# NB2_DBCON.net
KiCad netlist of a schematic drawn in Altium Designer
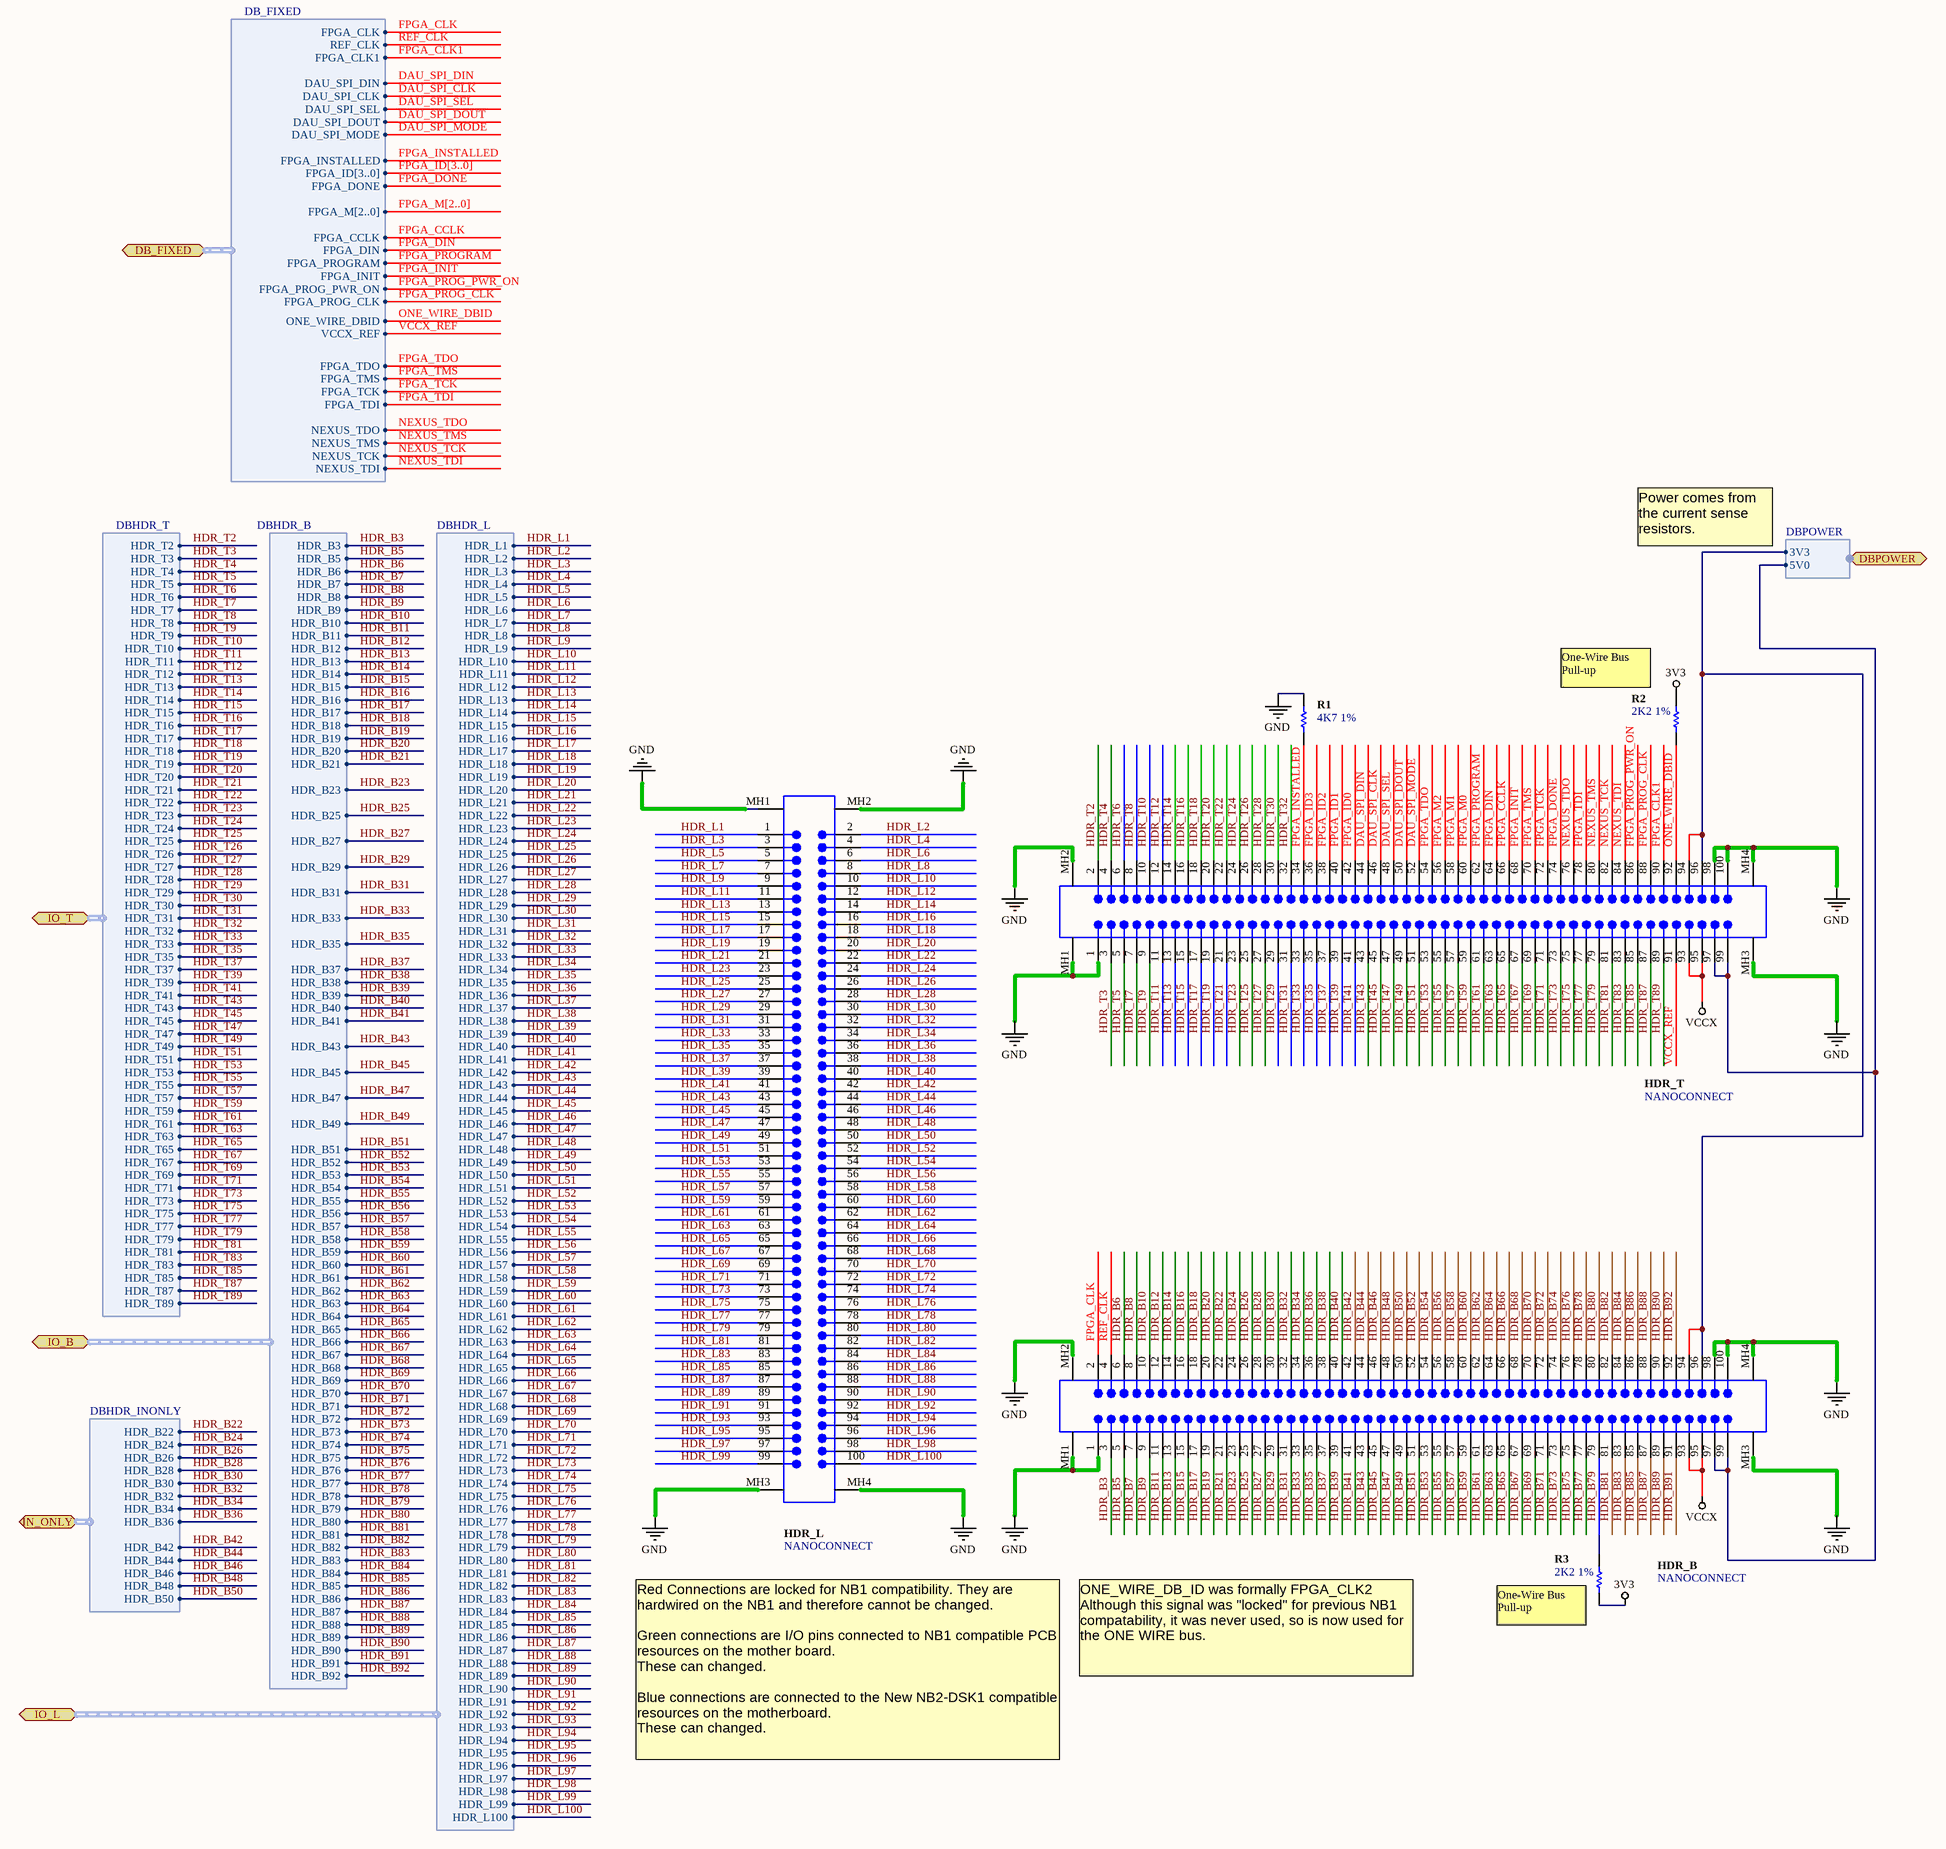
[diagram p0: NB2_DBCON.SchDoc]

(export (version "E")
  (design (tool "Eeschema 10.0.6"))
  (components
    (comp (ref "HDR_B")
      (value "NANOCONNECT")
      (footprint "53751")
      (description "Connector, Molex Docking Station 100 Pin Female 53751")
      (libsource (lib "altium-import") (part "root_1_CON-DOCKSTAT-100-F-STR_"))
    )
    (comp (ref "HDR_L")
      (value "NANOCONNECT")
      (footprint "53751")
      (description "Connector, Molex Docking Station 100 Pin Female 53751")
      (libsource (lib "altium-import") (part "root_0_CON-DOCKSTAT-100-F-STR_"))
    )
    (comp (ref "HDR_T")
      (value "NANOCONNECT")
      (footprint "53751")
      (description "Connector, Molex Docking Station 100 Pin Female 53751")
      (libsource (lib "altium-import") (part "root_1_CON-DOCKSTAT-100-F-STR_"))
    )
    (comp (ref "R1")
      (value "4K7 1%")
      (footprint "RESC1005-STAR")
      (description "Resistor, 4K7 1% 0402 (1005)")
      (fields (field (name "TOLERANCE") "1 %"))
      (libsource (lib "altium-import") (part "root_2_RES_"))
    )
    (comp (ref "R2")
      (value "2K2 1%")
      (footprint "RESC1005-STAR")
      (description "Resistor, 2K2 1% 0402 (1005)")
      (fields (field (name "TOLERANCE") "1 %"))
      (libsource (lib "altium-import") (part "root_2_RES_"))
    )
    (comp (ref "R3")
      (value "2K2 1%")
      (footprint "RESC1005-STAR")
      (description "Resistor, 2K2 1% 0402 (1005)")
      (fields (field (name "TOLERANCE") "1 %"))
      (libsource (lib "altium-import") (part "root_2_RES_"))
    )
  )
  (nets
    (net (code "7") (name "/DAU_SPI_CLK") (class "Default")
      (node (ref "HDR_T") (pin "46") (pinfunction "46_46") (pintype "passive"))
    )
    (net (code "8") (name "/DAU_SPI_DIN") (class "Default")
      (node (ref "HDR_T") (pin "44") (pinfunction "44_44") (pintype "passive"))
    )
    (net (code "9") (name "/DAU_SPI_DOUT") (class "Default")
      (node (ref "HDR_T") (pin "50") (pinfunction "50_50") (pintype "passive"))
    )
    (net (code "10") (name "/DAU_SPI_MODE") (class "Default")
      (node (ref "HDR_T") (pin "52") (pinfunction "52_52") (pintype "passive"))
    )
    (net (code "11") (name "/DAU_SPI_SEL") (class "Default")
      (node (ref "HDR_T") (pin "48") (pinfunction "48_48") (pintype "passive"))
    )
    (net (code "12") (name "/FPGA_CCLK") (class "Default")
      (node (ref "HDR_T") (pin "66") (pinfunction "66_66") (pintype "passive"))
    )
    (net (code "13") (name "/FPGA_CLK") (class "Default")
      (node (ref "HDR_B") (pin "2") (pinfunction "2_2") (pintype "passive"))
    )
    (net (code "14") (name "/FPGA_CLK1") (class "Default")
      (node (ref "HDR_T") (pin "90") (pinfunction "90_90") (pintype "passive"))
    )
    (net (code "15") (name "/FPGA_DIN") (class "Default")
      (node (ref "HDR_T") (pin "64") (pinfunction "64_64") (pintype "passive"))
    )
    (net (code "16") (name "/FPGA_DONE") (class "Default")
      (node (ref "HDR_T") (pin "74") (pinfunction "74_74") (pintype "passive"))
    )
    (net (code "17") (name "/FPGA_ID0") (class "Default")
      (node (ref "HDR_T") (pin "42") (pinfunction "42_42") (pintype "passive"))
    )
    (net (code "18") (name "/FPGA_ID1") (class "Default")
      (node (ref "HDR_T") (pin "40") (pinfunction "40_40") (pintype "passive"))
    )
    (net (code "19") (name "/FPGA_ID2") (class "Default")
      (node (ref "HDR_T") (pin "38") (pinfunction "38_38") (pintype "passive"))
    )
    (net (code "20") (name "/FPGA_ID3") (class "Default")
      (node (ref "HDR_T") (pin "36") (pinfunction "36_36") (pintype "passive"))
    )
    (net (code "22") (name "/FPGA_INIT") (class "Default")
      (node (ref "HDR_T") (pin "68") (pinfunction "68_68") (pintype "passive"))
    )
    (net (code "23") (name "/FPGA_INSTALLED") (class "Default")
      (node (ref "HDR_T") (pin "34") (pinfunction "34_34") (pintype "passive"))
      (node (ref "R1") (pin "1") (pinfunction "1_1") (pintype "passive"))
    )
    (net (code "24") (name "/FPGA_M0") (class "Default")
      (node (ref "HDR_T") (pin "60") (pinfunction "60_60") (pintype "passive"))
    )
    (net (code "25") (name "/FPGA_M1") (class "Default")
      (node (ref "HDR_T") (pin "58") (pinfunction "58_58") (pintype "passive"))
    )
    (net (code "26") (name "/FPGA_M2") (class "Default")
      (node (ref "HDR_T") (pin "56") (pinfunction "56_56") (pintype "passive"))
    )
    (net (code "28") (name "/FPGA_PROGRAM") (class "Default")
      (node (ref "HDR_T") (pin "62") (pinfunction "62_62") (pintype "passive"))
    )
    (net (code "29") (name "/FPGA_PROG_CLK") (class "Default")
      (node (ref "HDR_T") (pin "88") (pinfunction "88_88") (pintype "passive"))
    )
    (net (code "30") (name "/FPGA_PROG_PWR_ON") (class "Default")
      (node (ref "HDR_T") (pin "86") (pinfunction "86_86") (pintype "passive"))
    )
    (net (code "31") (name "/FPGA_TCK") (class "Default")
      (node (ref "HDR_T") (pin "72") (pinfunction "72_72") (pintype "passive"))
    )
    (net (code "32") (name "/FPGA_TDI") (class "Default")
      (node (ref "HDR_T") (pin "78") (pinfunction "78_78") (pintype "passive"))
    )
    (net (code "33") (name "/FPGA_TDO") (class "Default")
      (node (ref "HDR_T") (pin "54") (pinfunction "54_54") (pintype "passive"))
    )
    (net (code "34") (name "/FPGA_TMS") (class "Default")
      (node (ref "HDR_T") (pin "70") (pinfunction "70_70") (pintype "passive"))
    )
    (net (code "35") (name "/HDR_B3") (class "Default")
      (node (ref "HDR_B") (pin "3") (pinfunction "3_3") (pintype "passive"))
    )
    (net (code "36") (name "/HDR_B5") (class "Default")
      (node (ref "HDR_B") (pin "5") (pinfunction "5_5") (pintype "passive"))
    )
    (net (code "37") (name "/HDR_B6") (class "Default")
      (node (ref "HDR_B") (pin "6") (pinfunction "6_6") (pintype "passive"))
    )
    (net (code "38") (name "/HDR_B7") (class "Default")
      (node (ref "HDR_B") (pin "7") (pinfunction "7_7") (pintype "passive"))
    )
    (net (code "39") (name "/HDR_B8") (class "Default")
      (node (ref "HDR_B") (pin "8") (pinfunction "8_8") (pintype "passive"))
    )
    (net (code "40") (name "/HDR_B9") (class "Default")
      (node (ref "HDR_B") (pin "9") (pinfunction "9_9") (pintype "passive"))
    )
    (net (code "41") (name "/HDR_B10") (class "Default")
      (node (ref "HDR_B") (pin "10") (pinfunction "10_10") (pintype "passive"))
    )
    (net (code "42") (name "/HDR_B11") (class "Default")
      (node (ref "HDR_B") (pin "11") (pinfunction "11_11") (pintype "passive"))
    )
    (net (code "43") (name "/HDR_B12") (class "Default")
      (node (ref "HDR_B") (pin "12") (pinfunction "12_12") (pintype "passive"))
    )
    (net (code "44") (name "/HDR_B13") (class "Default")
      (node (ref "HDR_B") (pin "13") (pinfunction "13_13") (pintype "passive"))
    )
    (net (code "45") (name "/HDR_B14") (class "Default")
      (node (ref "HDR_B") (pin "14") (pinfunction "14_14") (pintype "passive"))
    )
    (net (code "46") (name "/HDR_B15") (class "Default")
      (node (ref "HDR_B") (pin "15") (pinfunction "15_15") (pintype "passive"))
    )
    (net (code "47") (name "/HDR_B16") (class "Default")
      (node (ref "HDR_B") (pin "16") (pinfunction "16_16") (pintype "passive"))
    )
    (net (code "48") (name "/HDR_B17") (class "Default")
      (node (ref "HDR_B") (pin "17") (pinfunction "17_17") (pintype "passive"))
    )
    (net (code "49") (name "/HDR_B18") (class "Default")
      (node (ref "HDR_B") (pin "18") (pinfunction "18_18") (pintype "passive"))
    )
    (net (code "50") (name "/HDR_B19") (class "Default")
      (node (ref "HDR_B") (pin "19") (pinfunction "19_19") (pintype "passive"))
    )
    (net (code "51") (name "/HDR_B20") (class "Default")
      (node (ref "HDR_B") (pin "20") (pinfunction "20_20") (pintype "passive"))
    )
    (net (code "52") (name "/HDR_B21") (class "Default")
      (node (ref "HDR_B") (pin "21") (pinfunction "21_21") (pintype "passive"))
    )
    (net (code "53") (name "/HDR_B22") (class "Default")
      (node (ref "HDR_B") (pin "22") (pinfunction "22_22") (pintype "passive"))
    )
    (net (code "54") (name "/HDR_B23") (class "Default")
      (node (ref "HDR_B") (pin "23") (pinfunction "23_23") (pintype "passive"))
    )
    (net (code "55") (name "/HDR_B24") (class "Default")
      (node (ref "HDR_B") (pin "24") (pinfunction "24_24") (pintype "passive"))
    )
    (net (code "56") (name "/HDR_B25") (class "Default")
      (node (ref "HDR_B") (pin "25") (pinfunction "25_25") (pintype "passive"))
    )
    (net (code "57") (name "/HDR_B26") (class "Default")
      (node (ref "HDR_B") (pin "26") (pinfunction "26_26") (pintype "passive"))
    )
    (net (code "58") (name "/HDR_B27") (class "Default")
      (node (ref "HDR_B") (pin "27") (pinfunction "27_27") (pintype "passive"))
    )
    (net (code "59") (name "/HDR_B28") (class "Default")
      (node (ref "HDR_B") (pin "28") (pinfunction "28_28") (pintype "passive"))
    )
    (net (code "60") (name "/HDR_B29") (class "Default")
      (node (ref "HDR_B") (pin "29") (pinfunction "29_29") (pintype "passive"))
    )
    (net (code "61") (name "/HDR_B30") (class "Default")
      (node (ref "HDR_B") (pin "30") (pinfunction "30_30") (pintype "passive"))
    )
    (net (code "62") (name "/HDR_B31") (class "Default")
      (node (ref "HDR_B") (pin "31") (pinfunction "31_31") (pintype "passive"))
    )
    (net (code "63") (name "/HDR_B32") (class "Default")
      (node (ref "HDR_B") (pin "32") (pinfunction "32_32") (pintype "passive"))
    )
    (net (code "64") (name "/HDR_B33") (class "Default")
      (node (ref "HDR_B") (pin "33") (pinfunction "33_33") (pintype "passive"))
    )
    (net (code "65") (name "/HDR_B34") (class "Default")
      (node (ref "HDR_B") (pin "34") (pinfunction "34_34") (pintype "passive"))
    )
    (net (code "66") (name "/HDR_B35") (class "Default")
      (node (ref "HDR_B") (pin "35") (pinfunction "35_35") (pintype "passive"))
    )
    (net (code "67") (name "/HDR_B36") (class "Default")
      (node (ref "HDR_B") (pin "36") (pinfunction "36_36") (pintype "passive"))
    )
    (net (code "68") (name "/HDR_B37") (class "Default")
      (node (ref "HDR_B") (pin "37") (pinfunction "37_37") (pintype "passive"))
    )
    (net (code "69") (name "/HDR_B38") (class "Default")
      (node (ref "HDR_B") (pin "38") (pinfunction "38_38") (pintype "passive"))
    )
    (net (code "70") (name "/HDR_B39") (class "Default")
      (node (ref "HDR_B") (pin "39") (pinfunction "39_39") (pintype "passive"))
    )
    (net (code "71") (name "/HDR_B40") (class "Default")
      (node (ref "HDR_B") (pin "40") (pinfunction "40_40") (pintype "passive"))
    )
    (net (code "72") (name "/HDR_B41") (class "Default")
      (node (ref "HDR_B") (pin "41") (pinfunction "41_41") (pintype "passive"))
    )
    (net (code "73") (name "/HDR_B42") (class "Default")
      (node (ref "HDR_B") (pin "42") (pinfunction "42_42") (pintype "passive"))
    )
    (net (code "74") (name "/HDR_B43") (class "Default")
      (node (ref "HDR_B") (pin "43") (pinfunction "43_43") (pintype "passive"))
    )
    (net (code "75") (name "/HDR_B44") (class "Default")
      (node (ref "HDR_B") (pin "44") (pinfunction "44_44") (pintype "passive"))
    )
    (net (code "76") (name "/HDR_B45") (class "Default")
      (node (ref "HDR_B") (pin "45") (pinfunction "45_45") (pintype "passive"))
    )
    (net (code "77") (name "/HDR_B46") (class "Default")
      (node (ref "HDR_B") (pin "46") (pinfunction "46_46") (pintype "passive"))
    )
    (net (code "78") (name "/HDR_B47") (class "Default")
      (node (ref "HDR_B") (pin "47") (pinfunction "47_47") (pintype "passive"))
    )
    (net (code "79") (name "/HDR_B48") (class "Default")
      (node (ref "HDR_B") (pin "48") (pinfunction "48_48") (pintype "passive"))
    )
    (net (code "80") (name "/HDR_B49") (class "Default")
      (node (ref "HDR_B") (pin "49") (pinfunction "49_49") (pintype "passive"))
    )
    (net (code "81") (name "/HDR_B50") (class "Default")
      (node (ref "HDR_B") (pin "50") (pinfunction "50_50") (pintype "passive"))
    )
    (net (code "82") (name "/HDR_B51") (class "Default")
      (node (ref "HDR_B") (pin "51") (pinfunction "51_51") (pintype "passive"))
    )
    (net (code "83") (name "/HDR_B52") (class "Default")
      (node (ref "HDR_B") (pin "52") (pinfunction "52_52") (pintype "passive"))
    )
    (net (code "84") (name "/HDR_B53") (class "Default")
      (node (ref "HDR_B") (pin "53") (pinfunction "53_53") (pintype "passive"))
    )
    (net (code "85") (name "/HDR_B54") (class "Default")
      (node (ref "HDR_B") (pin "54") (pinfunction "54_54") (pintype "passive"))
    )
    (net (code "86") (name "/HDR_B55") (class "Default")
      (node (ref "HDR_B") (pin "55") (pinfunction "55_55") (pintype "passive"))
    )
    (net (code "87") (name "/HDR_B56") (class "Default")
      (node (ref "HDR_B") (pin "56") (pinfunction "56_56") (pintype "passive"))
    )
    (net (code "88") (name "/HDR_B57") (class "Default")
      (node (ref "HDR_B") (pin "57") (pinfunction "57_57") (pintype "passive"))
    )
    (net (code "89") (name "/HDR_B58") (class "Default")
      (node (ref "HDR_B") (pin "58") (pinfunction "58_58") (pintype "passive"))
    )
    (net (code "90") (name "/HDR_B59") (class "Default")
      (node (ref "HDR_B") (pin "59") (pinfunction "59_59") (pintype "passive"))
    )
    (net (code "91") (name "/HDR_B60") (class "Default")
      (node (ref "HDR_B") (pin "60") (pinfunction "60_60") (pintype "passive"))
    )
    (net (code "92") (name "/HDR_B61") (class "Default")
      (node (ref "HDR_B") (pin "61") (pinfunction "61_61") (pintype "passive"))
    )
    (net (code "93") (name "/HDR_B62") (class "Default")
      (node (ref "HDR_B") (pin "62") (pinfunction "62_62") (pintype "passive"))
    )
    (net (code "94") (name "/HDR_B63") (class "Default")
      (node (ref "HDR_B") (pin "63") (pinfunction "63_63") (pintype "passive"))
    )
    (net (code "95") (name "/HDR_B64") (class "Default")
      (node (ref "HDR_B") (pin "64") (pinfunction "64_64") (pintype "passive"))
    )
    (net (code "96") (name "/HDR_B65") (class "Default")
      (node (ref "HDR_B") (pin "65") (pinfunction "65_65") (pintype "passive"))
    )
    (net (code "97") (name "/HDR_B66") (class "Default")
      (node (ref "HDR_B") (pin "66") (pinfunction "66_66") (pintype "passive"))
    )
    (net (code "98") (name "/HDR_B67") (class "Default")
      (node (ref "HDR_B") (pin "67") (pinfunction "67_67") (pintype "passive"))
    )
    (net (code "99") (name "/HDR_B68") (class "Default")
      (node (ref "HDR_B") (pin "68") (pinfunction "68_68") (pintype "passive"))
    )
    (net (code "100") (name "/HDR_B69") (class "Default")
      (node (ref "HDR_B") (pin "69") (pinfunction "69_69") (pintype "passive"))
    )
    (net (code "101") (name "/HDR_B70") (class "Default")
      (node (ref "HDR_B") (pin "70") (pinfunction "70_70") (pintype "passive"))
    )
    (net (code "102") (name "/HDR_B71") (class "Default")
      (node (ref "HDR_B") (pin "71") (pinfunction "71_71") (pintype "passive"))
    )
    (net (code "103") (name "/HDR_B72") (class "Default")
      (node (ref "HDR_B") (pin "72") (pinfunction "72_72") (pintype "passive"))
    )
    (net (code "104") (name "/HDR_B73") (class "Default")
      (node (ref "HDR_B") (pin "73") (pinfunction "73_73") (pintype "passive"))
    )
    (net (code "105") (name "/HDR_B74") (class "Default")
      (node (ref "HDR_B") (pin "74") (pinfunction "74_74") (pintype "passive"))
    )
    (net (code "106") (name "/HDR_B75") (class "Default")
      (node (ref "HDR_B") (pin "75") (pinfunction "75_75") (pintype "passive"))
    )
    (net (code "107") (name "/HDR_B76") (class "Default")
      (node (ref "HDR_B") (pin "76") (pinfunction "76_76") (pintype "passive"))
    )
    (net (code "108") (name "/HDR_B77") (class "Default")
      (node (ref "HDR_B") (pin "77") (pinfunction "77_77") (pintype "passive"))
    )
    (net (code "109") (name "/HDR_B78") (class "Default")
      (node (ref "HDR_B") (pin "78") (pinfunction "78_78") (pintype "passive"))
    )
    (net (code "110") (name "/HDR_B79") (class "Default")
      (node (ref "HDR_B") (pin "79") (pinfunction "79_79") (pintype "passive"))
      (node (ref "R3") (pin "2") (pinfunction "2_2") (pintype "passive"))
    )
    (net (code "111") (name "/HDR_B80") (class "Default")
      (node (ref "HDR_B") (pin "80") (pinfunction "80_80") (pintype "passive"))
    )
    (net (code "112") (name "/HDR_B81") (class "Default")
      (node (ref "HDR_B") (pin "81") (pinfunction "81_81") (pintype "passive"))
    )
    (net (code "113") (name "/HDR_B82") (class "Default")
      (node (ref "HDR_B") (pin "82") (pinfunction "82_82") (pintype "passive"))
    )
    (net (code "114") (name "/HDR_B83") (class "Default")
      (node (ref "HDR_B") (pin "83") (pinfunction "83_83") (pintype "passive"))
    )
    (net (code "115") (name "/HDR_B84") (class "Default")
      (node (ref "HDR_B") (pin "84") (pinfunction "84_84") (pintype "passive"))
    )
    (net (code "116") (name "/HDR_B85") (class "Default")
      (node (ref "HDR_B") (pin "85") (pinfunction "85_85") (pintype "passive"))
    )
    (net (code "117") (name "/HDR_B86") (class "Default")
      (node (ref "HDR_B") (pin "86") (pinfunction "86_86") (pintype "passive"))
    )
    (net (code "118") (name "/HDR_B87") (class "Default")
      (node (ref "HDR_B") (pin "87") (pinfunction "87_87") (pintype "passive"))
    )
    (net (code "119") (name "/HDR_B88") (class "Default")
      (node (ref "HDR_B") (pin "88") (pinfunction "88_88") (pintype "passive"))
    )
    (net (code "120") (name "/HDR_B89") (class "Default")
      (node (ref "HDR_B") (pin "89") (pinfunction "89_89") (pintype "passive"))
    )
    (net (code "121") (name "/HDR_B90") (class "Default")
      (node (ref "HDR_B") (pin "90") (pinfunction "90_90") (pintype "passive"))
    )
    (net (code "122") (name "/HDR_B91") (class "Default")
      (node (ref "HDR_B") (pin "91") (pinfunction "91_91") (pintype "passive"))
    )
    (net (code "123") (name "/HDR_B92") (class "Default")
      (node (ref "HDR_B") (pin "92") (pinfunction "92_92") (pintype "passive"))
    )
    (net (code "124") (name "/HDR_L1") (class "Default")
      (node (ref "HDR_L") (pin "1") (pinfunction "1_1") (pintype "passive"))
    )
    (net (code "125") (name "/HDR_L2") (class "Default")
      (node (ref "HDR_L") (pin "2") (pinfunction "2_2") (pintype "passive"))
    )
    (net (code "126") (name "/HDR_L3") (class "Default")
      (node (ref "HDR_L") (pin "3") (pinfunction "3_3") (pintype "passive"))
    )
    (net (code "127") (name "/HDR_L4") (class "Default")
      (node (ref "HDR_L") (pin "4") (pinfunction "4_4") (pintype "passive"))
    )
    (net (code "128") (name "/HDR_L5") (class "Default")
      (node (ref "HDR_L") (pin "5") (pinfunction "5_5") (pintype "passive"))
    )
    (net (code "129") (name "/HDR_L6") (class "Default")
      (node (ref "HDR_L") (pin "6") (pinfunction "6_6") (pintype "passive"))
    )
    (net (code "130") (name "/HDR_L7") (class "Default")
      (node (ref "HDR_L") (pin "7") (pinfunction "7_7") (pintype "passive"))
    )
    (net (code "131") (name "/HDR_L8") (class "Default")
      (node (ref "HDR_L") (pin "8") (pinfunction "8_8") (pintype "passive"))
    )
    (net (code "132") (name "/HDR_L9") (class "Default")
      (node (ref "HDR_L") (pin "9") (pinfunction "9_9") (pintype "passive"))
    )
    (net (code "133") (name "/HDR_L10") (class "Default")
      (node (ref "HDR_L") (pin "10") (pinfunction "10_10") (pintype "passive"))
    )
    (net (code "134") (name "/HDR_L11") (class "Default")
      (node (ref "HDR_L") (pin "11") (pinfunction "11_11") (pintype "passive"))
    )
    (net (code "135") (name "/HDR_L12") (class "Default")
      (node (ref "HDR_L") (pin "12") (pinfunction "12_12") (pintype "passive"))
    )
    (net (code "136") (name "/HDR_L13") (class "Default")
      (node (ref "HDR_L") (pin "13") (pinfunction "13_13") (pintype "passive"))
    )
    (net (code "137") (name "/HDR_L14") (class "Default")
      (node (ref "HDR_L") (pin "14") (pinfunction "14_14") (pintype "passive"))
    )
    (net (code "138") (name "/HDR_L15") (class "Default")
      (node (ref "HDR_L") (pin "15") (pinfunction "15_15") (pintype "passive"))
    )
    (net (code "139") (name "/HDR_L16") (class "Default")
      (node (ref "HDR_L") (pin "16") (pinfunction "16_16") (pintype "passive"))
    )
    (net (code "140") (name "/HDR_L17") (class "Default")
      (node (ref "HDR_L") (pin "17") (pinfunction "17_17") (pintype "passive"))
    )
    (net (code "141") (name "/HDR_L18") (class "Default")
      (node (ref "HDR_L") (pin "18") (pinfunction "18_18") (pintype "passive"))
    )
    (net (code "142") (name "/HDR_L19") (class "Default")
      (node (ref "HDR_L") (pin "19") (pinfunction "19_19") (pintype "passive"))
    )
    (net (code "143") (name "/HDR_L20") (class "Default")
      (node (ref "HDR_L") (pin "20") (pinfunction "20_20") (pintype "passive"))
    )
    (net (code "144") (name "/HDR_L21") (class "Default")
      (node (ref "HDR_L") (pin "21") (pinfunction "21_21") (pintype "passive"))
    )
    (net (code "145") (name "/HDR_L22") (class "Default")
      (node (ref "HDR_L") (pin "22") (pinfunction "22_22") (pintype "passive"))
    )
    (net (code "146") (name "/HDR_L23") (class "Default")
      (node (ref "HDR_L") (pin "23") (pinfunction "23_23") (pintype "passive"))
    )
    (net (code "147") (name "/HDR_L24") (class "Default")
      (node (ref "HDR_L") (pin "24") (pinfunction "24_24") (pintype "passive"))
    )
    (net (code "148") (name "/HDR_L25") (class "Default")
      (node (ref "HDR_L") (pin "25") (pinfunction "25_25") (pintype "passive"))
    )
    (net (code "149") (name "/HDR_L26") (class "Default")
      (node (ref "HDR_L") (pin "26") (pinfunction "26_26") (pintype "passive"))
    )
    (net (code "150") (name "/HDR_L27") (class "Default")
      (node (ref "HDR_L") (pin "27") (pinfunction "27_27") (pintype "passive"))
    )
    (net (code "151") (name "/HDR_L28") (class "Default")
      (node (ref "HDR_L") (pin "28") (pinfunction "28_28") (pintype "passive"))
    )
    (net (code "152") (name "/HDR_L29") (class "Default")
      (node (ref "HDR_L") (pin "29") (pinfunction "29_29") (pintype "passive"))
    )
    (net (code "153") (name "/HDR_L30") (class "Default")
      (node (ref "HDR_L") (pin "30") (pinfunction "30_30") (pintype "passive"))
    )
    (net (code "154") (name "/HDR_L31") (class "Default")
      (node (ref "HDR_L") (pin "31") (pinfunction "31_31") (pintype "passive"))
    )
    (net (code "155") (name "/HDR_L32") (class "Default")
      (node (ref "HDR_L") (pin "32") (pinfunction "32_32") (pintype "passive"))
    )
    (net (code "156") (name "/HDR_L33") (class "Default")
      (node (ref "HDR_L") (pin "33") (pinfunction "33_33") (pintype "passive"))
    )
    (net (code "157") (name "/HDR_L34") (class "Default")
      (node (ref "HDR_L") (pin "34") (pinfunction "34_34") (pintype "passive"))
    )
    (net (code "158") (name "/HDR_L35") (class "Default")
      (node (ref "HDR_L") (pin "35") (pinfunction "35_35") (pintype "passive"))
    )
    (net (code "159") (name "/HDR_L36") (class "Default")
      (node (ref "HDR_L") (pin "36") (pinfunction "36_36") (pintype "passive"))
    )
    (net (code "160") (name "/HDR_L37") (class "Default")
      (node (ref "HDR_L") (pin "37") (pinfunction "37_37") (pintype "passive"))
    )
    (net (code "161") (name "/HDR_L38") (class "Default")
      (node (ref "HDR_L") (pin "38") (pinfunction "38_38") (pintype "passive"))
    )
    (net (code "162") (name "/HDR_L39") (class "Default")
      (node (ref "HDR_L") (pin "39") (pinfunction "39_39") (pintype "passive"))
    )
    (net (code "163") (name "/HDR_L40") (class "Default")
      (node (ref "HDR_L") (pin "40") (pinfunction "40_40") (pintype "passive"))
    )
    (net (code "164") (name "/HDR_L41") (class "Default")
      (node (ref "HDR_L") (pin "41") (pinfunction "41_41") (pintype "passive"))
    )
    (net (code "165") (name "/HDR_L42") (class "Default")
      (node (ref "HDR_L") (pin "42") (pinfunction "42_42") (pintype "passive"))
    )
    (net (code "166") (name "/HDR_L43") (class "Default")
      (node (ref "HDR_L") (pin "43") (pinfunction "43_43") (pintype "passive"))
    )
    (net (code "167") (name "/HDR_L44") (class "Default")
      (node (ref "HDR_L") (pin "44") (pinfunction "44_44") (pintype "passive"))
    )
    (net (code "168") (name "/HDR_L45") (class "Default")
      (node (ref "HDR_L") (pin "45") (pinfunction "45_45") (pintype "passive"))
    )
    (net (code "169") (name "/HDR_L46") (class "Default")
      (node (ref "HDR_L") (pin "46") (pinfunction "46_46") (pintype "passive"))
    )
    (net (code "170") (name "/HDR_L47") (class "Default")
      (node (ref "HDR_L") (pin "47") (pinfunction "47_47") (pintype "passive"))
    )
    (net (code "171") (name "/HDR_L48") (class "Default")
      (node (ref "HDR_L") (pin "48") (pinfunction "48_48") (pintype "passive"))
    )
    (net (code "172") (name "/HDR_L49") (class "Default")
      (node (ref "HDR_L") (pin "49") (pinfunction "49_49") (pintype "passive"))
    )
    (net (code "173") (name "/HDR_L50") (class "Default")
      (node (ref "HDR_L") (pin "50") (pinfunction "50_50") (pintype "passive"))
    )
    (net (code "174") (name "/HDR_L51") (class "Default")
      (node (ref "HDR_L") (pin "51") (pinfunction "51_51") (pintype "passive"))
    )
    (net (code "175") (name "/HDR_L52") (class "Default")
      (node (ref "HDR_L") (pin "52") (pinfunction "52_52") (pintype "passive"))
    )
    (net (code "176") (name "/HDR_L53") (class "Default")
      (node (ref "HDR_L") (pin "53") (pinfunction "53_53") (pintype "passive"))
    )
    (net (code "177") (name "/HDR_L54") (class "Default")
      (node (ref "HDR_L") (pin "54") (pinfunction "54_54") (pintype "passive"))
    )
    (net (code "178") (name "/HDR_L55") (class "Default")
      (node (ref "HDR_L") (pin "55") (pinfunction "55_55") (pintype "passive"))
    )
    (net (code "179") (name "/HDR_L56") (class "Default")
      (node (ref "HDR_L") (pin "56") (pinfunction "56_56") (pintype "passive"))
    )
    (net (code "180") (name "/HDR_L57") (class "Default")
      (node (ref "HDR_L") (pin "57") (pinfunction "57_57") (pintype "passive"))
    )
    (net (code "181") (name "/HDR_L58") (class "Default")
      (node (ref "HDR_L") (pin "58") (pinfunction "58_58") (pintype "passive"))
    )
    (net (code "182") (name "/HDR_L59") (class "Default")
      (node (ref "HDR_L") (pin "59") (pinfunction "59_59") (pintype "passive"))
    )
    (net (code "183") (name "/HDR_L60") (class "Default")
      (node (ref "HDR_L") (pin "60") (pinfunction "60_60") (pintype "passive"))
    )
    (net (code "184") (name "/HDR_L61") (class "Default")
      (node (ref "HDR_L") (pin "61") (pinfunction "61_61") (pintype "passive"))
    )
    (net (code "185") (name "/HDR_L62") (class "Default")
      (node (ref "HDR_L") (pin "62") (pinfunction "62_62") (pintype "passive"))
    )
    (net (code "186") (name "/HDR_L63") (class "Default")
      (node (ref "HDR_L") (pin "63") (pinfunction "63_63") (pintype "passive"))
    )
    (net (code "187") (name "/HDR_L64") (class "Default")
      (node (ref "HDR_L") (pin "64") (pinfunction "64_64") (pintype "passive"))
    )
    (net (code "188") (name "/HDR_L65") (class "Default")
      (node (ref "HDR_L") (pin "65") (pinfunction "65_65") (pintype "passive"))
    )
    (net (code "189") (name "/HDR_L66") (class "Default")
      (node (ref "HDR_L") (pin "66") (pinfunction "66_66") (pintype "passive"))
    )
    (net (code "190") (name "/HDR_L67") (class "Default")
      (node (ref "HDR_L") (pin "67") (pinfunction "67_67") (pintype "passive"))
    )
    (net (code "191") (name "/HDR_L68") (class "Default")
      (node (ref "HDR_L") (pin "68") (pinfunction "68_68") (pintype "passive"))
    )
    (net (code "192") (name "/HDR_L69") (class "Default")
      (node (ref "HDR_L") (pin "69") (pinfunction "69_69") (pintype "passive"))
    )
    (net (code "193") (name "/HDR_L70") (class "Default")
      (node (ref "HDR_L") (pin "70") (pinfunction "70_70") (pintype "passive"))
    )
    (net (code "194") (name "/HDR_L71") (class "Default")
      (node (ref "HDR_L") (pin "71") (pinfunction "71_71") (pintype "passive"))
    )
    (net (code "195") (name "/HDR_L72") (class "Default")
      (node (ref "HDR_L") (pin "72") (pinfunction "72_72") (pintype "passive"))
    )
    (net (code "196") (name "/HDR_L73") (class "Default")
      (node (ref "HDR_L") (pin "73") (pinfunction "73_73") (pintype "passive"))
    )
    (net (code "197") (name "/HDR_L74") (class "Default")
      (node (ref "HDR_L") (pin "74") (pinfunction "74_74") (pintype "passive"))
    )
    (net (code "198") (name "/HDR_L75") (class "Default")
      (node (ref "HDR_L") (pin "75") (pinfunction "75_75") (pintype "passive"))
    )
    (net (code "199") (name "/HDR_L76") (class "Default")
      (node (ref "HDR_L") (pin "76") (pinfunction "76_76") (pintype "passive"))
    )
    (net (code "200") (name "/HDR_L77") (class "Default")
      (node (ref "HDR_L") (pin "77") (pinfunction "77_77") (pintype "passive"))
    )
    (net (code "201") (name "/HDR_L78") (class "Default")
      (node (ref "HDR_L") (pin "78") (pinfunction "78_78") (pintype "passive"))
    )
    (net (code "202") (name "/HDR_L79") (class "Default")
      (node (ref "HDR_L") (pin "79") (pinfunction "79_79") (pintype "passive"))
    )
    (net (code "203") (name "/HDR_L80") (class "Default")
      (node (ref "HDR_L") (pin "80") (pinfunction "80_80") (pintype "passive"))
    )
    (net (code "204") (name "/HDR_L81") (class "Default")
      (node (ref "HDR_L") (pin "81") (pinfunction "81_81") (pintype "passive"))
    )
    (net (code "205") (name "/HDR_L82") (class "Default")
      (node (ref "HDR_L") (pin "82") (pinfunction "82_82") (pintype "passive"))
    )
    (net (code "206") (name "/HDR_L83") (class "Default")
      (node (ref "HDR_L") (pin "83") (pinfunction "83_83") (pintype "passive"))
    )
    (net (code "207") (name "/HDR_L84") (class "Default")
      (node (ref "HDR_L") (pin "84") (pinfunction "84_84") (pintype "passive"))
    )
    (net (code "208") (name "/HDR_L85") (class "Default")
      (node (ref "HDR_L") (pin "85") (pinfunction "85_85") (pintype "passive"))
    )
    (net (code "209") (name "/HDR_L86") (class "Default")
      (node (ref "HDR_L") (pin "86") (pinfunction "86_86") (pintype "passive"))
    )
    (net (code "210") (name "/HDR_L87") (class "Default")
      (node (ref "HDR_L") (pin "87") (pinfunction "87_87") (pintype "passive"))
    )
    (net (code "211") (name "/HDR_L88") (class "Default")
      (node (ref "HDR_L") (pin "88") (pinfunction "88_88") (pintype "passive"))
    )
    (net (code "212") (name "/HDR_L89") (class "Default")
      (node (ref "HDR_L") (pin "89") (pinfunction "89_89") (pintype "passive"))
    )
    (net (code "213") (name "/HDR_L90") (class "Default")
      (node (ref "HDR_L") (pin "90") (pinfunction "90_90") (pintype "passive"))
    )
    (net (code "214") (name "/HDR_L91") (class "Default")
      (node (ref "HDR_L") (pin "91") (pinfunction "91_91") (pintype "passive"))
    )
    (net (code "215") (name "/HDR_L92") (class "Default")
      (node (ref "HDR_L") (pin "92") (pinfunction "92_92") (pintype "passive"))
    )
    (net (code "216") (name "/HDR_L93") (class "Default")
      (node (ref "HDR_L") (pin "93") (pinfunction "93_93") (pintype "passive"))
    )
    (net (code "217") (name "/HDR_L94") (class "Default")
      (node (ref "HDR_L") (pin "94") (pinfunction "94_94") (pintype "passive"))
    )
    (net (code "218") (name "/HDR_L95") (class "Default")
      (node (ref "HDR_L") (pin "95") (pinfunction "95_95") (pintype "passive"))
    )
    (net (code "219") (name "/HDR_L96") (class "Default")
      (node (ref "HDR_L") (pin "96") (pinfunction "96_96") (pintype "passive"))
    )
    (net (code "220") (name "/HDR_L97") (class "Default")
      (node (ref "HDR_L") (pin "97") (pinfunction "97_97") (pintype "passive"))
    )
    (net (code "221") (name "/HDR_L98") (class "Default")
      (node (ref "HDR_L") (pin "98") (pinfunction "98_98") (pintype "passive"))
    )
    (net (code "222") (name "/HDR_L99") (class "Default")
      (node (ref "HDR_L") (pin "99") (pinfunction "99_99") (pintype "passive"))
    )
    (net (code "223") (name "/HDR_L100") (class "Default")
      (node (ref "HDR_L") (pin "100") (pinfunction "100_100") (pintype "passive"))
    )
    (net (code "224") (name "/HDR_T2") (class "Default")
      (node (ref "HDR_T") (pin "2") (pinfunction "2_2") (pintype "passive"))
    )
    (net (code "225") (name "/HDR_T3") (class "Default")
      (node (ref "HDR_T") (pin "3") (pinfunction "3_3") (pintype "passive"))
    )
    (net (code "226") (name "/HDR_T4") (class "Default")
      (node (ref "HDR_T") (pin "4") (pinfunction "4_4") (pintype "passive"))
    )
    (net (code "227") (name "/HDR_T5") (class "Default")
      (node (ref "HDR_T") (pin "5") (pinfunction "5_5") (pintype "passive"))
    )
    (net (code "228") (name "/HDR_T6") (class "Default")
      (node (ref "HDR_T") (pin "6") (pinfunction "6_6") (pintype "passive"))
    )
    (net (code "229") (name "/HDR_T7") (class "Default")
      (node (ref "HDR_T") (pin "7") (pinfunction "7_7") (pintype "passive"))
    )
    (net (code "230") (name "/HDR_T8") (class "Default")
      (node (ref "HDR_T") (pin "8") (pinfunction "8_8") (pintype "passive"))
    )
    (net (code "231") (name "/HDR_T9") (class "Default")
      (node (ref "HDR_T") (pin "9") (pinfunction "9_9") (pintype "passive"))
    )
    (net (code "232") (name "/HDR_T10") (class "Default")
      (node (ref "HDR_T") (pin "10") (pinfunction "10_10") (pintype "passive"))
    )
    (net (code "233") (name "/HDR_T11") (class "Default")
      (node (ref "HDR_T") (pin "11") (pinfunction "11_11") (pintype "passive"))
    )
    (net (code "234") (name "/HDR_T12") (class "Default")
      (node (ref "HDR_T") (pin "12") (pinfunction "12_12") (pintype "passive"))
    )
    (net (code "235") (name "/HDR_T13") (class "Default")
      (node (ref "HDR_T") (pin "13") (pinfunction "13_13") (pintype "passive"))
    )
    (net (code "236") (name "/HDR_T14") (class "Default")
      (node (ref "HDR_T") (pin "14") (pinfunction "14_14") (pintype "passive"))
    )
    (net (code "237") (name "/HDR_T15") (class "Default")
      (node (ref "HDR_T") (pin "15") (pinfunction "15_15") (pintype "passive"))
    )
    (net (code "238") (name "/HDR_T16") (class "Default")
      (node (ref "HDR_T") (pin "16") (pinfunction "16_16") (pintype "passive"))
    )
    (net (code "239") (name "/HDR_T17") (class "Default")
      (node (ref "HDR_T") (pin "17") (pinfunction "17_17") (pintype "passive"))
    )
    (net (code "240") (name "/HDR_T18") (class "Default")
      (node (ref "HDR_T") (pin "18") (pinfunction "18_18") (pintype "passive"))
    )
    (net (code "241") (name "/HDR_T19") (class "Default")
      (node (ref "HDR_T") (pin "19") (pinfunction "19_19") (pintype "passive"))
    )
    (net (code "242") (name "/HDR_T20") (class "Default")
      (node (ref "HDR_T") (pin "20") (pinfunction "20_20") (pintype "passive"))
    )
    (net (code "243") (name "/HDR_T21") (class "Default")
      (node (ref "HDR_T") (pin "21") (pinfunction "21_21") (pintype "passive"))
    )
    (net (code "244") (name "/HDR_T22") (class "Default")
      (node (ref "HDR_T") (pin "22") (pinfunction "22_22") (pintype "passive"))
    )
    (net (code "245") (name "/HDR_T23") (class "Default")
      (node (ref "HDR_T") (pin "23") (pinfunction "23_23") (pintype "passive"))
    )
    (net (code "246") (name "/HDR_T24") (class "Default")
      (node (ref "HDR_T") (pin "24") (pinfunction "24_24") (pintype "passive"))
    )
    (net (code "247") (name "/HDR_T25") (class "Default")
      (node (ref "HDR_T") (pin "25") (pinfunction "25_25") (pintype "passive"))
    )
    (net (code "248") (name "/HDR_T26") (class "Default")
      (node (ref "HDR_T") (pin "26") (pinfunction "26_26") (pintype "passive"))
    )
    (net (code "249") (name "/HDR_T27") (class "Default")
      (node (ref "HDR_T") (pin "27") (pinfunction "27_27") (pintype "passive"))
    )
    (net (code "250") (name "/HDR_T28") (class "Default")
      (node (ref "HDR_T") (pin "28") (pinfunction "28_28") (pintype "passive"))
    )
    (net (code "251") (name "/HDR_T29") (class "Default")
      (node (ref "HDR_T") (pin "29") (pinfunction "29_29") (pintype "passive"))
    )
    (net (code "252") (name "/HDR_T30") (class "Default")
      (node (ref "HDR_T") (pin "30") (pinfunction "30_30") (pintype "passive"))
    )
    (net (code "253") (name "/HDR_T31") (class "Default")
      (node (ref "HDR_T") (pin "31") (pinfunction "31_31") (pintype "passive"))
    )
    (net (code "254") (name "/HDR_T32") (class "Default")
      (node (ref "HDR_T") (pin "32") (pinfunction "32_32") (pintype "passive"))
    )
    (net (code "255") (name "/HDR_T33") (class "Default")
      (node (ref "HDR_T") (pin "33") (pinfunction "33_33") (pintype "passive"))
    )
    (net (code "256") (name "/HDR_T35") (class "Default")
      (node (ref "HDR_T") (pin "35") (pinfunction "35_35") (pintype "passive"))
    )
    (net (code "257") (name "/HDR_T37") (class "Default")
      (node (ref "HDR_T") (pin "37") (pinfunction "37_37") (pintype "passive"))
    )
    (net (code "258") (name "/HDR_T39") (class "Default")
      (node (ref "HDR_T") (pin "39") (pinfunction "39_39") (pintype "passive"))
    )
    (net (code "259") (name "/HDR_T41") (class "Default")
      (node (ref "HDR_T") (pin "41") (pinfunction "41_41") (pintype "passive"))
    )
    (net (code "260") (name "/HDR_T43") (class "Default")
      (node (ref "HDR_T") (pin "43") (pinfunction "43_43") (pintype "passive"))
    )
    (net (code "261") (name "/HDR_T45") (class "Default")
      (node (ref "HDR_T") (pin "45") (pinfunction "45_45") (pintype "passive"))
    )
    (net (code "262") (name "/HDR_T47") (class "Default")
      (node (ref "HDR_T") (pin "47") (pinfunction "47_47") (pintype "passive"))
    )
    (net (code "263") (name "/HDR_T49") (class "Default")
      (node (ref "HDR_T") (pin "49") (pinfunction "49_49") (pintype "passive"))
    )
    (net (code "264") (name "/HDR_T51") (class "Default")
      (node (ref "HDR_T") (pin "51") (pinfunction "51_51") (pintype "passive"))
    )
    (net (code "265") (name "/HDR_T53") (class "Default")
      (node (ref "HDR_T") (pin "53") (pinfunction "53_53") (pintype "passive"))
    )
    (net (code "266") (name "/HDR_T55") (class "Default")
      (node (ref "HDR_T") (pin "55") (pinfunction "55_55") (pintype "passive"))
    )
    (net (code "267") (name "/HDR_T57") (class "Default")
      (node (ref "HDR_T") (pin "57") (pinfunction "57_57") (pintype "passive"))
    )
    (net (code "268") (name "/HDR_T59") (class "Default")
      (node (ref "HDR_T") (pin "59") (pinfunction "59_59") (pintype "passive"))
    )
    (net (code "269") (name "/HDR_T61") (class "Default")
      (node (ref "HDR_T") (pin "61") (pinfunction "61_61") (pintype "passive"))
    )
    (net (code "270") (name "/HDR_T63") (class "Default")
      (node (ref "HDR_T") (pin "63") (pinfunction "63_63") (pintype "passive"))
    )
    (net (code "271") (name "/HDR_T65") (class "Default")
      (node (ref "HDR_T") (pin "65") (pinfunction "65_65") (pintype "passive"))
    )
    (net (code "272") (name "/HDR_T67") (class "Default")
      (node (ref "HDR_T") (pin "67") (pinfunction "67_67") (pintype "passive"))
    )
    (net (code "273") (name "/HDR_T69") (class "Default")
      (node (ref "HDR_T") (pin "69") (pinfunction "69_69") (pintype "passive"))
    )
    (net (code "274") (name "/HDR_T71") (class "Default")
      (node (ref "HDR_T") (pin "71") (pinfunction "71_71") (pintype "passive"))
    )
    (net (code "275") (name "/HDR_T73") (class "Default")
      (node (ref "HDR_T") (pin "73") (pinfunction "73_73") (pintype "passive"))
    )
    (net (code "276") (name "/HDR_T75") (class "Default")
      (node (ref "HDR_T") (pin "75") (pinfunction "75_75") (pintype "passive"))
    )
    (net (code "277") (name "/HDR_T77") (class "Default")
      (node (ref "HDR_T") (pin "77") (pinfunction "77_77") (pintype "passive"))
    )
    (net (code "278") (name "/HDR_T79") (class "Default")
      (node (ref "HDR_T") (pin "79") (pinfunction "79_79") (pintype "passive"))
    )
    (net (code "279") (name "/HDR_T81") (class "Default")
      (node (ref "HDR_T") (pin "81") (pinfunction "81_81") (pintype "passive"))
    )
    (net (code "280") (name "/HDR_T83") (class "Default")
      (node (ref "HDR_T") (pin "83") (pinfunction "83_83") (pintype "passive"))
    )
    (net (code "281") (name "/HDR_T85") (class "Default")
      (node (ref "HDR_T") (pin "85") (pinfunction "85_85") (pintype "passive"))
    )
    (net (code "282") (name "/HDR_T87") (class "Default")
      (node (ref "HDR_T") (pin "87") (pinfunction "87_87") (pintype "passive"))
    )
    (net (code "283") (name "/HDR_T89") (class "Default")
      (node (ref "HDR_T") (pin "89") (pinfunction "89_89") (pintype "passive"))
    )
    (net (code "284") (name "/NEXUS_TCK") (class "Default")
      (node (ref "HDR_T") (pin "82") (pinfunction "82_82") (pintype "passive"))
    )
    (net (code "285") (name "/NEXUS_TDI") (class "Default")
      (node (ref "HDR_T") (pin "84") (pinfunction "84_84") (pintype "passive"))
    )
    (net (code "286") (name "/NEXUS_TDO") (class "Default")
      (node (ref "HDR_T") (pin "76") (pinfunction "76_76") (pintype "passive"))
    )
    (net (code "287") (name "/NEXUS_TMS") (class "Default")
      (node (ref "HDR_T") (pin "80") (pinfunction "80_80") (pintype "passive"))
    )
    (net (code "288") (name "/ONE_WIRE_DBID") (class "Default")
      (node (ref "HDR_T") (pin "92") (pinfunction "92_92") (pintype "passive"))
      (node (ref "R2") (pin "1") (pinfunction "1_1") (pintype "passive"))
    )
    (net (code "289") (name "/REF_CLK") (class "Default")
      (node (ref "HDR_B") (pin "4") (pinfunction "4_4") (pintype "passive"))
    )
    (net (code "290") (name "/VCCX_REF") (class "Default")
      (node (ref "HDR_T") (pin "91") (pinfunction "91_91") (pintype "passive"))
    )
    (net (code "297") (name "3V3") (class "Default")
      (node (ref "R2") (pin "2") (pinfunction "2_2") (pintype "passive"))
      (node (ref "R3") (pin "1") (pinfunction "1_1") (pintype "passive"))
    )
    (net (code "298") (name "GND") (class "Default")
      (node (ref "HDR_B") (pin "1") (pinfunction "1_1") (pintype "passive"))
      (node (ref "HDR_B") (pin "100") (pinfunction "100_100") (pintype "passive"))
      (node (ref "HDR_B") (pin "98") (pinfunction "98_98") (pintype "passive"))
      (node (ref "HDR_B") (pin "MH1") (pinfunction "MH1_MH1") (pintype "passive"))
      (node (ref "HDR_B") (pin "MH2") (pinfunction "MH2_MH2") (pintype "passive"))
      (node (ref "HDR_B") (pin "MH3") (pinfunction "MH3_MH3") (pintype "passive"))
      (node (ref "HDR_B") (pin "MH4") (pinfunction "MH4_MH4") (pintype "passive"))
      (node (ref "HDR_L") (pin "MH1") (pinfunction "MH1_MH1") (pintype "passive"))
      (node (ref "HDR_L") (pin "MH2") (pinfunction "MH2_MH2") (pintype "passive"))
      (node (ref "HDR_L") (pin "MH3") (pinfunction "MH3_MH3") (pintype "passive"))
      (node (ref "HDR_L") (pin "MH4") (pinfunction "MH4_MH4") (pintype "passive"))
      (node (ref "HDR_T") (pin "1") (pinfunction "1_1") (pintype "passive"))
      (node (ref "HDR_T") (pin "100") (pinfunction "100_100") (pintype "passive"))
      (node (ref "HDR_T") (pin "98") (pinfunction "98_98") (pintype "passive"))
      (node (ref "HDR_T") (pin "MH1") (pinfunction "MH1_MH1") (pintype "passive"))
      (node (ref "HDR_T") (pin "MH2") (pinfunction "MH2_MH2") (pintype "passive"))
      (node (ref "HDR_T") (pin "MH3") (pinfunction "MH3_MH3") (pintype "passive"))
      (node (ref "HDR_T") (pin "MH4") (pinfunction "MH4_MH4") (pintype "passive"))
      (node (ref "R1") (pin "2") (pinfunction "2_2") (pintype "passive"))
    )
    (net (code "299") (name "Net-(HDR_B-Pad94)") (class "Default")
      (node (ref "HDR_B") (pin "94") (pinfunction "94_94") (pintype "passive"))
      (node (ref "HDR_B") (pin "96") (pinfunction "96_96") (pintype "passive"))
      (node (ref "HDR_T") (pin "94") (pinfunction "94_94") (pintype "passive"))
      (node (ref "HDR_T") (pin "96") (pinfunction "96_96") (pintype "passive"))
    )
    (net (code "300") (name "Net-(HDR_B-Pad97)") (class "Default")
      (node (ref "HDR_B") (pin "97") (pinfunction "97_97") (pintype "passive"))
      (node (ref "HDR_B") (pin "99") (pinfunction "99_99") (pintype "passive"))
      (node (ref "HDR_T") (pin "97") (pinfunction "97_97") (pintype "passive"))
      (node (ref "HDR_T") (pin "99") (pinfunction "99_99") (pintype "passive"))
    )
    (net (code "301") (name "VCCX") (class "Default")
      (node (ref "HDR_B") (pin "93") (pinfunction "93_93") (pintype "passive"))
      (node (ref "HDR_B") (pin "95") (pinfunction "95_95") (pintype "passive"))
      (node (ref "HDR_T") (pin "93") (pinfunction "93_93") (pintype "passive"))
      (node (ref "HDR_T") (pin "95") (pinfunction "95_95") (pintype "passive"))
    )
  )
)
